# sensori_di_linea_soccer_2018.net
KiCad netlist of a schematic drawn in EAGLE
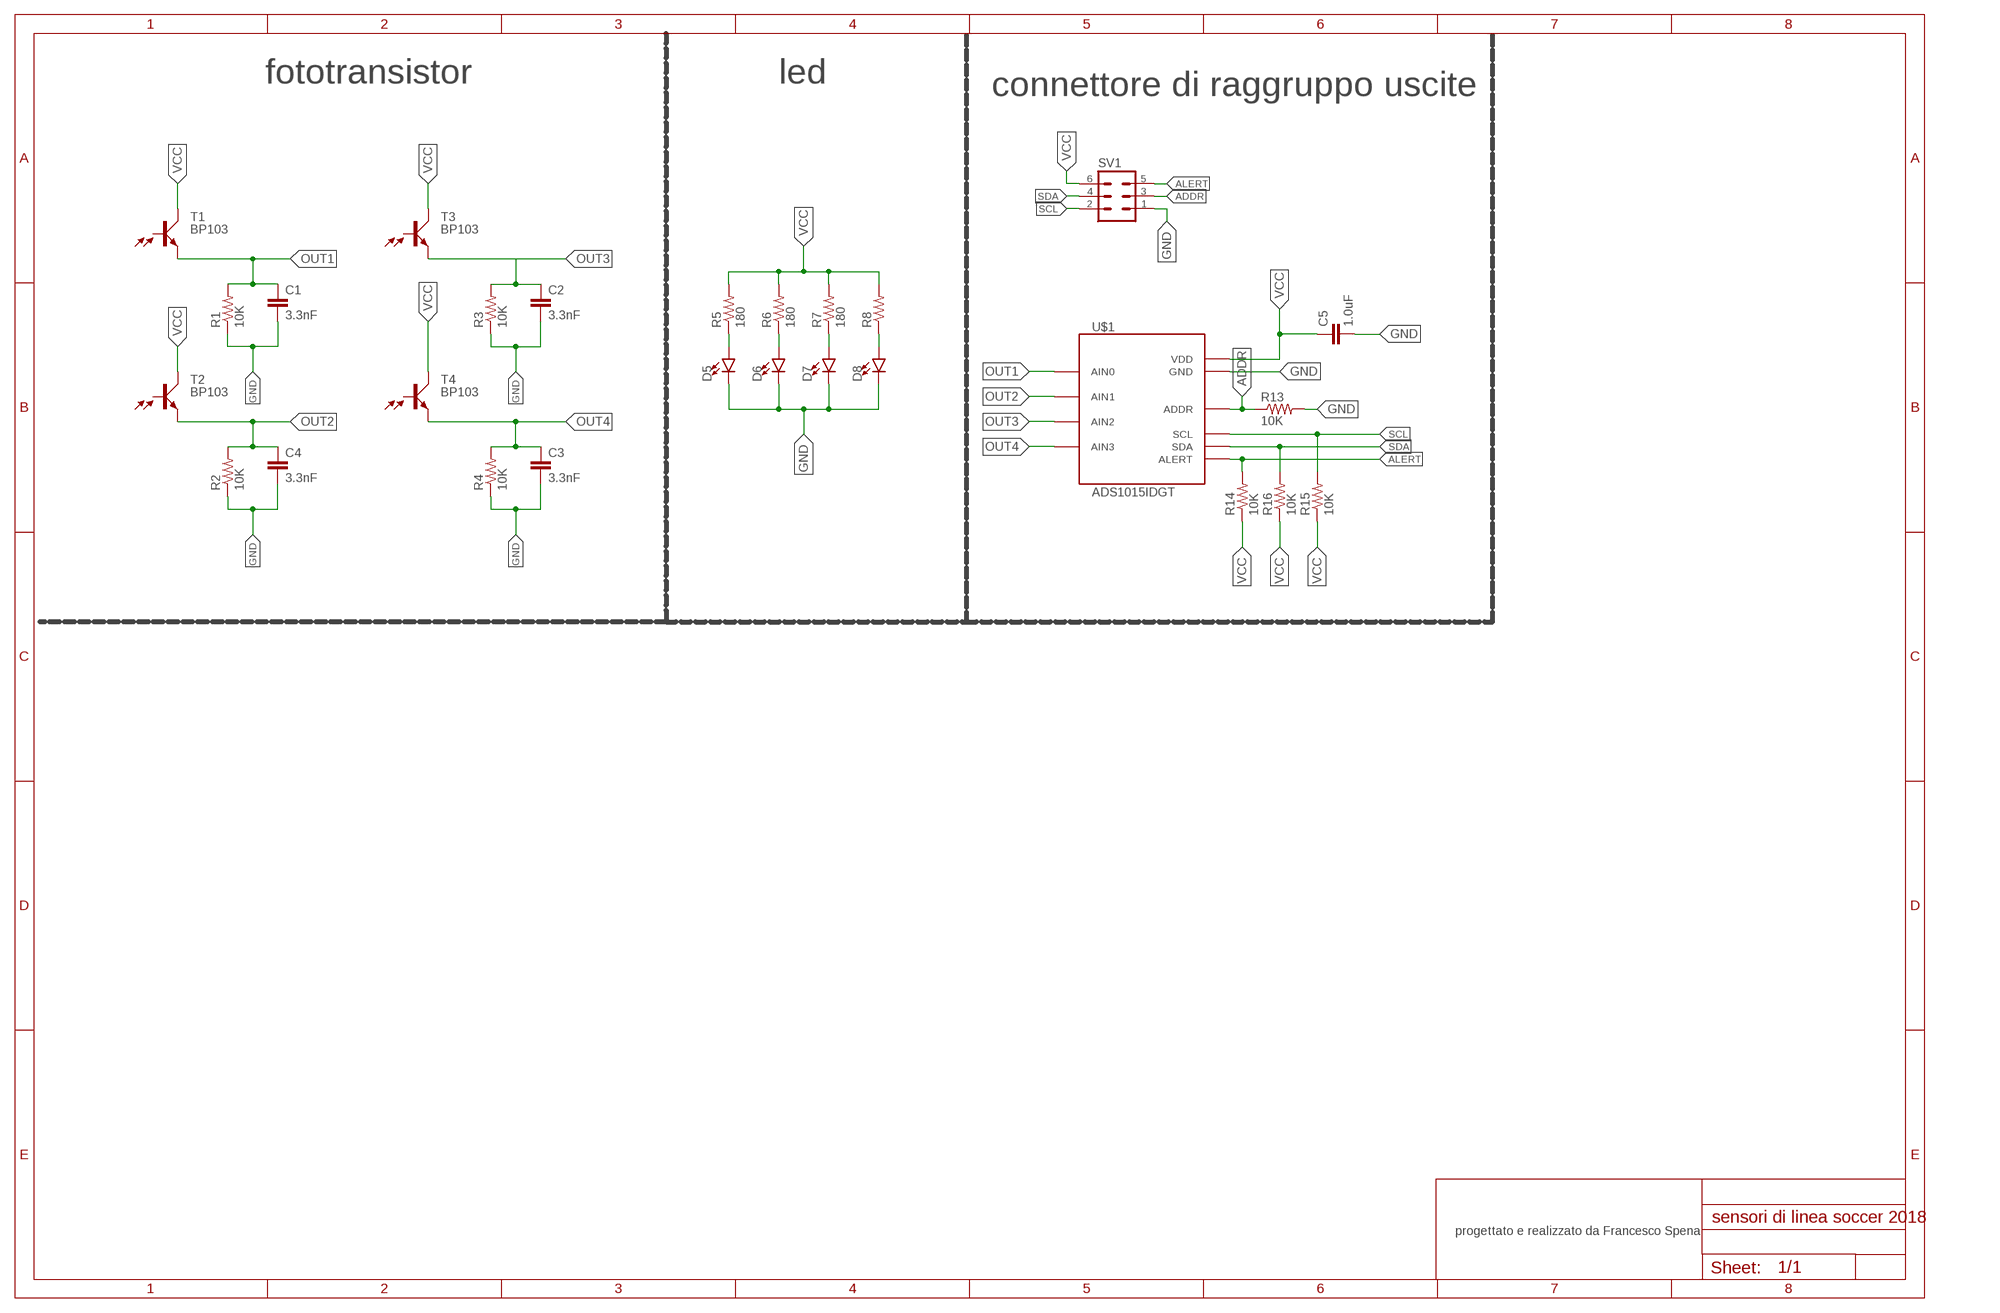
[diagram p0: schematic, sheet 1]

(export (version "E")
  (design (tool "Eeschema 10.0.6"))
  (components
    (comp (ref "C1")
      (value "3.3nF")
      (footprint "eagle-import:0603")
      (libsource (lib "eagle-import") (part "3.3NF-0603-100V-10%"))
    )
    (comp (ref "C2")
      (value "3.3nF")
      (footprint "eagle-import:0603")
      (libsource (lib "eagle-import") (part "3.3NF-0603-100V-10%"))
    )
    (comp (ref "C3")
      (value "3.3nF")
      (footprint "eagle-import:0603")
      (libsource (lib "eagle-import") (part "3.3NF-0603-100V-10%"))
    )
    (comp (ref "C4")
      (value "3.3nF")
      (footprint "eagle-import:0603")
      (libsource (lib "eagle-import") (part "3.3NF-0603-100V-10%"))
    )
    (comp (ref "C5")
      (value "1.0uF")
      (footprint "eagle-import:0402")
      (libsource (lib "eagle-import") (part "1.0UF-0402-16V-10%"))
    )
    (comp (ref "D5")
      (value "LED3MM")
      (footprint "eagle-import:LED_3MM")
      (libsource (lib "eagle-import") (part "LED3MM"))
    )
    (comp (ref "D6")
      (value "LED3MM")
      (footprint "eagle-import:LED_3MM")
      (libsource (lib "eagle-import") (part "LED3MM"))
    )
    (comp (ref "D7")
      (value "LED3MM")
      (footprint "eagle-import:LED_3MM")
      (libsource (lib "eagle-import") (part "LED3MM"))
    )
    (comp (ref "D8")
      (value "LED3MM")
      (footprint "eagle-import:LED_3MM")
      (libsource (lib "eagle-import") (part "LED3MM"))
    )
    (comp (ref "R1")
      (value "10K")
      (footprint "eagle-import:0204_7")
      (libsource (lib "eagle-import") (part "resistor_348_R-US_0204/7"))
    )
    (comp (ref "R2")
      (value "10K")
      (footprint "eagle-import:0204_7")
      (libsource (lib "eagle-import") (part "resistor_348_R-US_0204/7"))
    )
    (comp (ref "R3")
      (value "10K")
      (footprint "eagle-import:0204_7")
      (libsource (lib "eagle-import") (part "resistor_348_R-US_0204/7"))
    )
    (comp (ref "R4")
      (value "10K")
      (footprint "eagle-import:0204_7")
      (libsource (lib "eagle-import") (part "resistor_348_R-US_0204/7"))
    )
    (comp (ref "R5")
      (value "180")
      (footprint "eagle-import:0204_7")
      (libsource (lib "eagle-import") (part "R-US_0204/7"))
    )
    (comp (ref "R6")
      (value "180")
      (footprint "eagle-import:0204_7")
      (libsource (lib "eagle-import") (part "R-US_0204/7"))
    )
    (comp (ref "R7")
      (value "180")
      (footprint "eagle-import:0204_7")
      (libsource (lib "eagle-import") (part "R-US_0204/7"))
    )
    (comp (ref "R8")
      (value "R-US_0204/7")
      (footprint "eagle-import:0204_7")
      (libsource (lib "eagle-import") (part "R-US_0204/7"))
    )
    (comp (ref "R13")
      (value "10K")
      (footprint "eagle-import:0204_7")
      (libsource (lib "eagle-import") (part "resistor_348_R-US_0204/7"))
    )
    (comp (ref "R14")
      (value "10K")
      (footprint "eagle-import:0204_7")
      (libsource (lib "eagle-import") (part "resistor_348_R-US_0204/7"))
    )
    (comp (ref "R15")
      (value "10K")
      (footprint "eagle-import:0204_7")
      (libsource (lib "eagle-import") (part "resistor_348_R-US_0204/7"))
    )
    (comp (ref "R16")
      (value "10K")
      (footprint "eagle-import:0204_7")
      (libsource (lib "eagle-import") (part "resistor_348_R-US_0204/7"))
    )
    (comp (ref "SV1")
      (value "MA03-2")
      (footprint "eagle-import:MA03-2")
      (libsource (lib "eagle-import") (part "MA03-2"))
    )
    (comp (ref "T1")
      (value "BP103")
      (footprint "eagle-import:BP103")
      (libsource (lib "eagle-import") (part "BP103"))
    )
    (comp (ref "T2")
      (value "BP103")
      (footprint "eagle-import:BP103")
      (libsource (lib "eagle-import") (part "BP103"))
    )
    (comp (ref "T3")
      (value "BP103")
      (footprint "eagle-import:BP103")
      (libsource (lib "eagle-import") (part "BP103"))
    )
    (comp (ref "T4")
      (value "BP103")
      (footprint "eagle-import:BP103")
      (libsource (lib "eagle-import") (part "BP103"))
    )
    (comp (ref "U$1")
      (value "ADS1015IDGT")
      (footprint "eagle-import:MSOP10_0.5")
      (libsource (lib "eagle-import") (part "ADS1015IDGT"))
    )
  )
  (nets
    (net (code "1") (name "ADDR") (class "Default")
      (node (ref "R13") (pin "1") (pinfunction "1_1") (pintype "passive"))
      (node (ref "SV1") (pin "3") (pinfunction "3_3") (pintype "passive"))
      (node (ref "U$1") (pin "1") (pinfunction "ADDR_1") (pintype "input"))
    )
    (net (code "2") (name "ALERT") (class "Default")
      (node (ref "R14") (pin "2") (pinfunction "2_2") (pintype "passive"))
      (node (ref "SV1") (pin "5") (pinfunction "5_5") (pintype "passive"))
      (node (ref "U$1") (pin "2") (pinfunction "ALERT_2") (pintype "output"))
    )
    (net (code "3") (name "GND") (class "Default")
      (node (ref "C1") (pin "2") (pinfunction "2_2") (pintype "passive"))
      (node (ref "C2") (pin "2") (pinfunction "2_2") (pintype "passive"))
      (node (ref "C3") (pin "2") (pinfunction "2_2") (pintype "passive"))
      (node (ref "C4") (pin "2") (pinfunction "2_2") (pintype "passive"))
      (node (ref "C5") (pin "2") (pinfunction "2_2") (pintype "passive"))
      (node (ref "D5") (pin "K") (pinfunction "C_K") (pintype "passive"))
      (node (ref "D6") (pin "K") (pinfunction "C_K") (pintype "passive"))
      (node (ref "D7") (pin "K") (pinfunction "C_K") (pintype "passive"))
      (node (ref "D8") (pin "K") (pinfunction "C_K") (pintype "passive"))
      (node (ref "R1") (pin "1") (pinfunction "1_1") (pintype "passive"))
      (node (ref "R13") (pin "2") (pinfunction "2_2") (pintype "passive"))
      (node (ref "R2") (pin "1") (pinfunction "1_1") (pintype "passive"))
      (node (ref "R3") (pin "1") (pinfunction "1_1") (pintype "passive"))
      (node (ref "R4") (pin "1") (pinfunction "1_1") (pintype "passive"))
      (node (ref "SV1") (pin "1") (pinfunction "1_1") (pintype "passive"))
      (node (ref "U$1") (pin "3") (pinfunction "GND_3") (pintype "power_in"))
    )
    (net (code "4") (name "Net-(D5-PadA)") (class "Default")
      (node (ref "D5") (pin "A") (pinfunction "A_A") (pintype "passive"))
      (node (ref "R5") (pin "1") (pinfunction "1_1") (pintype "passive"))
    )
    (net (code "5") (name "Net-(D6-PadA)") (class "Default")
      (node (ref "D6") (pin "A") (pinfunction "A_A") (pintype "passive"))
      (node (ref "R6") (pin "1") (pinfunction "1_1") (pintype "passive"))
    )
    (net (code "6") (name "Net-(D7-PadA)") (class "Default")
      (node (ref "D7") (pin "A") (pinfunction "A_A") (pintype "passive"))
      (node (ref "R7") (pin "1") (pinfunction "1_1") (pintype "passive"))
    )
    (net (code "7") (name "Net-(D8-PadA)") (class "Default")
      (node (ref "D8") (pin "A") (pinfunction "A_A") (pintype "passive"))
      (node (ref "R8") (pin "1") (pinfunction "1_1") (pintype "passive"))
    )
    (net (code "8") (name "OUT1") (class "Default")
      (node (ref "C1") (pin "1") (pinfunction "1_1") (pintype "passive"))
      (node (ref "R1") (pin "2") (pinfunction "2_2") (pintype "passive"))
      (node (ref "T1") (pin "E") (pinfunction "E_E") (pintype "passive"))
      (node (ref "U$1") (pin "4") (pinfunction "AIN0_4") (pintype "input"))
    )
    (net (code "9") (name "OUT2") (class "Default")
      (node (ref "C4") (pin "1") (pinfunction "1_1") (pintype "passive"))
      (node (ref "R2") (pin "2") (pinfunction "2_2") (pintype "passive"))
      (node (ref "T2") (pin "E") (pinfunction "E_E") (pintype "passive"))
      (node (ref "U$1") (pin "5") (pinfunction "AIN1_5") (pintype "input"))
    )
    (net (code "10") (name "OUT3") (class "Default")
      (node (ref "C2") (pin "1") (pinfunction "1_1") (pintype "passive"))
      (node (ref "R3") (pin "2") (pinfunction "2_2") (pintype "passive"))
      (node (ref "T3") (pin "E") (pinfunction "E_E") (pintype "passive"))
      (node (ref "U$1") (pin "6") (pinfunction "AIN2_6") (pintype "input"))
    )
    (net (code "11") (name "OUT4") (class "Default")
      (node (ref "C3") (pin "1") (pinfunction "1_1") (pintype "passive"))
      (node (ref "R4") (pin "2") (pinfunction "2_2") (pintype "passive"))
      (node (ref "T4") (pin "E") (pinfunction "E_E") (pintype "passive"))
      (node (ref "U$1") (pin "7") (pinfunction "AIN3_7") (pintype "input"))
    )
    (net (code "12") (name "SCL") (class "Default")
      (node (ref "R15") (pin "2") (pinfunction "2_2") (pintype "passive"))
      (node (ref "SV1") (pin "2") (pinfunction "2_2") (pintype "passive"))
      (node (ref "U$1") (pin "10") (pinfunction "SCL_10") (pintype "bidirectional"))
    )
    (net (code "13") (name "SDA") (class "Default")
      (node (ref "R16") (pin "2") (pinfunction "2_2") (pintype "passive"))
      (node (ref "SV1") (pin "4") (pinfunction "4_4") (pintype "passive"))
      (node (ref "U$1") (pin "9") (pinfunction "SDA_9") (pintype "bidirectional"))
    )
    (net (code "14") (name "VCC") (class "Default")
      (node (ref "C5") (pin "1") (pinfunction "1_1") (pintype "passive"))
      (node (ref "R14") (pin "1") (pinfunction "1_1") (pintype "passive"))
      (node (ref "R15") (pin "1") (pinfunction "1_1") (pintype "passive"))
      (node (ref "R16") (pin "1") (pinfunction "1_1") (pintype "passive"))
      (node (ref "R5") (pin "2") (pinfunction "2_2") (pintype "passive"))
      (node (ref "R6") (pin "2") (pinfunction "2_2") (pintype "passive"))
      (node (ref "R7") (pin "2") (pinfunction "2_2") (pintype "passive"))
      (node (ref "R8") (pin "2") (pinfunction "2_2") (pintype "passive"))
      (node (ref "SV1") (pin "6") (pinfunction "6_6") (pintype "passive"))
      (node (ref "T1") (pin "C") (pinfunction "C_C") (pintype "passive"))
      (node (ref "T2") (pin "C") (pinfunction "C_C") (pintype "passive"))
      (node (ref "T3") (pin "C") (pinfunction "C_C") (pintype "passive"))
      (node (ref "T4") (pin "C") (pinfunction "C_C") (pintype "passive"))
      (node (ref "U$1") (pin "8") (pinfunction "VDD_8") (pintype "power_in"))
    )
    (net (code "15") (name "unconnected-(T1-PadB)") (class "Default")
      (node (ref "T1") (pin "B") (pinfunction "B_B") (pintype "passive"))
    )
    (net (code "16") (name "unconnected-(T2-PadB)") (class "Default")
      (node (ref "T2") (pin "B") (pinfunction "B_B") (pintype "passive"))
    )
    (net (code "17") (name "unconnected-(T3-PadB)") (class "Default")
      (node (ref "T3") (pin "B") (pinfunction "B_B") (pintype "passive"))
    )
    (net (code "18") (name "unconnected-(T4-PadB)") (class "Default")
      (node (ref "T4") (pin "B") (pinfunction "B_B") (pintype "passive"))
    )
  )
)
